# BANK34.net
KiCad netlist of a schematic drawn in Altium Designer
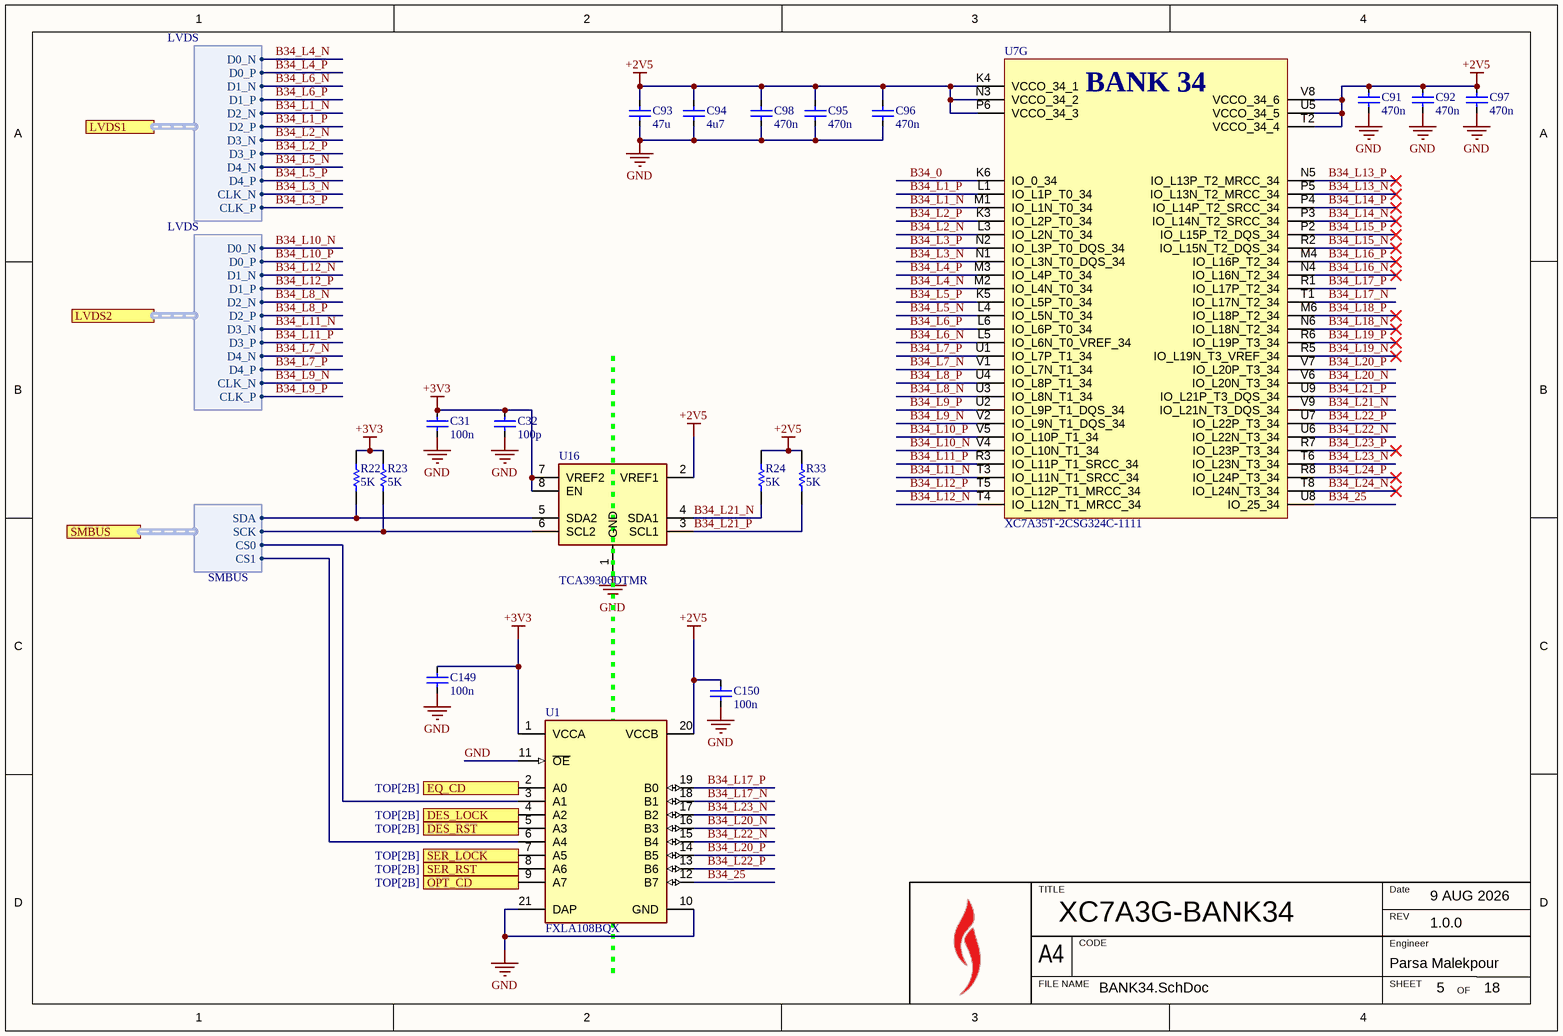
[diagram p0: BANK34.SchDoc]

(export (version "E")
  (design (tool "Eeschema 10.0.6"))
  (components
    (comp (ref "C31")
      (value "100n")
      (footprint "FP-C1005-050-0_05-IPC_C")
      (description "MLCC 100nF ±10% 50V X7R SMD 0402")
      (fields (field (name "VOLTAGE") "50V") (field (name "TOLERANCE") "10%"))
      (libsource (lib "Schlib1") (part "C1005X7R1H104K050BB"))
    )
    (comp (ref "C32")
      (value "100p")
      (footprint "FP-C1005-050-0_05-IPC_C")
      (description "MLCC 100pF ±5% 50V C0G SMD 0402")
      (fields (field (name "TOLERANCE") "5%") (field (name "VOLTAGE") "50V"))
      (libsource (lib "Schlib1") (part "C1005C0G1H101J050BA"))
    )
    (comp (ref "C91")
      (value "470n")
      (footprint "pcblib1:FP-C1005-050-0_05-IPC_C")
      (description "Multilayer Ceramic Capacitors 470nF ±10% 25V X5R SMD 0402")
      (fields (field (name "VOLTAGE") "25V") (field (name "TOLERANCE") "10%"))
      (libsource (lib "Schlib1") (part "C1005X5R1E474K050BB"))
    )
    (comp (ref "C92")
      (value "470n")
      (footprint "pcblib1:FP-C1005-050-0_05-IPC_C")
      (description "Multilayer Ceramic Capacitors 470nF ±10% 25V X5R SMD 0402")
      (fields (field (name "VOLTAGE") "25V") (field (name "TOLERANCE") "10%"))
      (libsource (lib "Schlib1") (part "C1005X5R1E474K050BB"))
    )
    (comp (ref "C93")
      (value "47u")
      (footprint "FP-C2012-125-0_2-IPC_C")
      (description "47μF ±20% 10V X5R SMD 0805 Multilayer Ceramic Capacitors")
      (fields (field (name "VOLTAGE") "10V") (field (name "TOLERANCE") "20%"))
      (libsource (lib "Schlib1") (part "C2012X5R1A476M125AC"))
    )
    (comp (ref "C94")
      (value "4u7")
      (footprint "FP-C1005-050-0_20-0_10-IPC_C")
      (description "4.7UF 10V X5R 0402")
      (fields (field (name "TOLERANCE") "10%") (field (name "PART NUMBER") "C1005X5R1A475K050BE"))
      (libsource (lib "Schlib1") (part "C1005X5R1A475K050BE"))
    )
    (comp (ref "C95")
      (value "470n")
      (footprint "pcblib1:FP-C1005-050-0_05-IPC_C")
      (description "Multilayer Ceramic Capacitors 470nF ±10% 25V X5R SMD 0402")
      (fields (field (name "VOLTAGE") "25V") (field (name "TOLERANCE") "10%"))
      (libsource (lib "Schlib1") (part "C1005X5R1E474K050BB"))
    )
    (comp (ref "C96")
      (value "470n")
      (footprint "pcblib1:FP-C1005-050-0_05-IPC_C")
      (description "Multilayer Ceramic Capacitors 470nF ±10% 25V X5R SMD 0402")
      (fields (field (name "VOLTAGE") "25V") (field (name "TOLERANCE") "10%"))
      (libsource (lib "Schlib1") (part "C1005X5R1E474K050BB"))
    )
    (comp (ref "C97")
      (value "470n")
      (footprint "pcblib1:FP-C1005-050-0_05-IPC_C")
      (description "Multilayer Ceramic Capacitors 470nF ±10% 25V X5R SMD 0402")
      (fields (field (name "VOLTAGE") "25V") (field (name "TOLERANCE") "10%"))
      (libsource (lib "Schlib1") (part "C1005X5R1E474K050BB"))
    )
    (comp (ref "C98")
      (value "470n")
      (footprint "pcblib1:FP-C1005-050-0_05-IPC_C")
      (description "Multilayer Ceramic Capacitors 470nF ±10% 25V X5R SMD 0402")
      (fields (field (name "VOLTAGE") "25V") (field (name "TOLERANCE") "10%"))
      (libsource (lib "Schlib1") (part "C1005X5R1E474K050BB"))
    )
    (comp (ref "C149")
      (value "100n")
      (footprint "FP-C1005-050-0_05-IPC_C")
      (description "MLCC 100nF ±10% 50V X7R SMD 0402")
      (fields (field (name "VOLTAGE") "50V") (field (name "TOLERANCE") "10%"))
      (libsource (lib "Schlib1") (part "C1005X7R1H104K050BB"))
    )
    (comp (ref "C150")
      (value "100n")
      (footprint "FP-C1005-050-0_05-IPC_C")
      (description "MLCC 100nF ±10% 50V X7R SMD 0402")
      (fields (field (name "VOLTAGE") "50V") (field (name "TOLERANCE") "10%"))
      (libsource (lib "Schlib1") (part "C1005X7R1H104K050BB"))
    )
    (comp (ref "R22")
      (value "5K")
      (footprint "RESC1005X40X25LL05T10")
      (description "62.5mW Thick Film Resistors 50V ±100ppm/℃ ±1% 5kΩ 0402 Chip Resistor - Surface Mount ROHS")
      (fields (field (name "MANUFACTURER") "Yageo / Phycomp") (field (name "PART NUMBER") "RC0402FR-075KL"))
      (libsource (lib "Schlib1") (part "RC0402FR-075KL"))
    )
    (comp (ref "R23")
      (value "5K")
      (footprint "RESC1005X40X25LL05T10")
      (description "62.5mW Thick Film Resistors 50V ±100ppm/℃ ±1% 5kΩ 0402 Chip Resistor - Surface Mount ROHS")
      (fields (field (name "MANUFACTURER") "Yageo / Phycomp") (field (name "PART NUMBER") "RC0402FR-075KL"))
      (libsource (lib "Schlib1") (part "RC0402FR-075KL"))
    )
    (comp (ref "R24")
      (value "5K")
      (footprint "RESC1005X40X25LL05T10")
      (description "62.5mW Thick Film Resistors 50V ±100ppm/℃ ±1% 5kΩ 0402 Chip Resistor - Surface Mount ROHS")
      (fields (field (name "MANUFACTURER") "Yageo / Phycomp") (field (name "PART NUMBER") "RC0402FR-075KL"))
      (libsource (lib "Schlib1") (part "RC0402FR-075KL"))
    )
    (comp (ref "R33")
      (value "5K")
      (footprint "RESC1005X40X25LL05T10")
      (description "62.5mW Thick Film Resistors 50V ±100ppm/℃ ±1% 5kΩ 0402 Chip Resistor - Surface Mount ROHS")
      (fields (field (name "MANUFACTURER") "Yageo / Phycomp") (field (name "PART NUMBER") "RC0402FR-075KL"))
      (libsource (lib "Schlib1") (part "RC0402FR-075KL"))
    )
    (comp (ref "U1")
      (value "FXLA108BQX")
      (footprint "FP-510CD-MFG")
      (description "IC TRNSLTR BIDIRECTIONAL 20DQFN")
      (fields
        (field (name "MANUFACTURER") "ON Semiconductor")
        (field (name "OCTOPART") "https://octopart.com/fxla108bqx-on+semiconductor-84328716")
      )
      (libsource (lib "Schlib1") (part "FXLA108BQX"))
    )
    (comp (ref "U7")
      (value "XC7A35T-2CSG324C-1111")
      (footprint "PCBLIB1:BGA324C80P18X18_1500X1500X150")
      (description "Integrated Circuit")
      (fields
        (field (name "MANUFACTURER_PART_NUMBER") "XC7A35T-2CSG324C")
        (field (name "MOUSER PART NUMBER") "217-XC7A35T-2CSG324C")
      )
      (libsource (lib "Schlib1") (part "XC7A35T-2CSG324C-1111"))
    )
    (comp (ref "U16")
      (value "TCA39306DTMR")
      (footprint "TCA39306DTMR")
      (description "Integrated Circuit")
      (fields (field (name "MOUSER PART NUMBER") "595-TCA39306DTMR"))
      (libsource (lib "Schlib1") (part "TCA39306DTMR"))
    )
  )
  (nets
    (net (code "3") (name "+2V5") (class "Default")
      (node (ref "C150") (pin "1") (pinfunction "1_1") (pintype "passive"))
      (node (ref "C91") (pin "1") (pinfunction "1_1") (pintype "passive"))
      (node (ref "C92") (pin "1") (pinfunction "1_1") (pintype "passive"))
      (node (ref "C93") (pin "1") (pinfunction "1_1") (pintype "passive"))
      (node (ref "C94") (pin "1") (pinfunction "1_1") (pintype "passive"))
      (node (ref "C95") (pin "1") (pinfunction "1_1") (pintype "passive"))
      (node (ref "C96") (pin "1") (pinfunction "1_1") (pintype "passive"))
      (node (ref "C97") (pin "1") (pinfunction "1_1") (pintype "passive"))
      (node (ref "C98") (pin "1") (pinfunction "1_1") (pintype "passive"))
      (node (ref "R24") (pin "1") (pinfunction "1_1") (pintype "passive"))
      (node (ref "R33") (pin "1") (pinfunction "1_1") (pintype "passive"))
      (node (ref "U1") (pin "20") (pinfunction "VCCB_20") (pintype "power_in"))
      (node (ref "U16") (pin "2") (pinfunction "VREF1_2") (pintype "passive"))
      (node (ref "U7") (pin "K4") (pinfunction "VCCO_34_1_K4") (pintype "passive"))
      (node (ref "U7") (pin "N3") (pinfunction "VCCO_34_2_N3") (pintype "passive"))
      (node (ref "U7") (pin "P6") (pinfunction "VCCO_34_3_P6") (pintype "passive"))
      (node (ref "U7") (pin "T2") (pinfunction "VCCO_34_4_T2") (pintype "passive"))
      (node (ref "U7") (pin "U5") (pinfunction "VCCO_34_5_U5") (pintype "passive"))
      (node (ref "U7") (pin "V8") (pinfunction "VCCO_34_6_V8") (pintype "passive"))
    )
    (net (code "4") (name "+3V3") (class "Default")
      (node (ref "C149") (pin "1") (pinfunction "1_1") (pintype "passive"))
      (node (ref "C31") (pin "1") (pinfunction "1_1") (pintype "passive"))
      (node (ref "C32") (pin "1") (pinfunction "1_1") (pintype "passive"))
      (node (ref "R22") (pin "1") (pinfunction "1_1") (pintype "passive"))
      (node (ref "R23") (pin "1") (pinfunction "1_1") (pintype "passive"))
      (node (ref "U1") (pin "1") (pinfunction "VCCA_1") (pintype "power_in"))
      (node (ref "U16") (pin "7") (pinfunction "VREF2_7") (pintype "passive"))
      (node (ref "U16") (pin "8") (pinfunction "EN_8") (pintype "passive"))
    )
    (net (code "5") (name "/B34_0") (class "Default")
      (node (ref "U7") (pin "K6") (pinfunction "IO_0_34_K6") (pintype "passive"))
    )
    (net (code "6") (name "/B34_25") (class "Default")
      (node (ref "U1") (pin "12") (pinfunction "B7_12") (pintype "bidirectional"))
      (node (ref "U7") (pin "U8") (pinfunction "IO_25_34_U8") (pintype "passive"))
    )
    (net (code "7") (name "/B34_L1_N") (class "Default")
      (node (ref "U7") (pin "M1") (pinfunction "IO_L1N_T0_34_M1") (pintype "passive"))
    )
    (net (code "8") (name "/B34_L1_P") (class "Default")
      (node (ref "U7") (pin "L1") (pinfunction "IO_L1P_T0_34_L1") (pintype "passive"))
    )
    (net (code "9") (name "/B34_L2_N") (class "Default")
      (node (ref "U7") (pin "L3") (pinfunction "IO_L2N_T0_34_L3") (pintype "passive"))
    )
    (net (code "10") (name "/B34_L2_P") (class "Default")
      (node (ref "U7") (pin "K3") (pinfunction "IO_L2P_T0_34_K3") (pintype "passive"))
    )
    (net (code "11") (name "/B34_L3_N") (class "Default")
      (node (ref "U7") (pin "N1") (pinfunction "IO_L3N_T0_DQS_34_N1") (pintype "passive"))
    )
    (net (code "12") (name "/B34_L3_P") (class "Default")
      (node (ref "U7") (pin "N2") (pinfunction "IO_L3P_T0_DQS_34_N2") (pintype "passive"))
    )
    (net (code "13") (name "/B34_L4_N") (class "Default")
      (node (ref "U7") (pin "M2") (pinfunction "IO_L4N_T0_34_M2") (pintype "passive"))
    )
    (net (code "14") (name "/B34_L4_P") (class "Default")
      (node (ref "U7") (pin "M3") (pinfunction "IO_L4P_T0_34_M3") (pintype "passive"))
    )
    (net (code "15") (name "/B34_L5_N") (class "Default")
      (node (ref "U7") (pin "L4") (pinfunction "IO_L5N_T0_34_L4") (pintype "passive"))
    )
    (net (code "16") (name "/B34_L5_P") (class "Default")
      (node (ref "U7") (pin "K5") (pinfunction "IO_L5P_T0_34_K5") (pintype "passive"))
    )
    (net (code "17") (name "/B34_L6_N") (class "Default")
      (node (ref "U7") (pin "L5") (pinfunction "IO_L6N_T0_VREF_34_L5") (pintype "passive"))
    )
    (net (code "18") (name "/B34_L6_P") (class "Default")
      (node (ref "U7") (pin "L6") (pinfunction "IO_L6P_T0_34_L6") (pintype "passive"))
    )
    (net (code "19") (name "/B34_L7_N") (class "Default")
      (node (ref "U7") (pin "V1") (pinfunction "IO_L7N_T1_34_V1") (pintype "passive"))
    )
    (net (code "20") (name "/B34_L7_P") (class "Default")
      (node (ref "U7") (pin "U1") (pinfunction "IO_L7P_T1_34_U1") (pintype "passive"))
    )
    (net (code "21") (name "/B34_L8_N") (class "Default")
      (node (ref "U7") (pin "U3") (pinfunction "IO_L8N_T1_34_U3") (pintype "passive"))
    )
    (net (code "22") (name "/B34_L8_P") (class "Default")
      (node (ref "U7") (pin "U4") (pinfunction "IO_L8P_T1_34_U4") (pintype "passive"))
    )
    (net (code "23") (name "/B34_L9_N") (class "Default")
      (node (ref "U7") (pin "V2") (pinfunction "IO_L9N_T1_DQS_34_V2") (pintype "passive"))
    )
    (net (code "24") (name "/B34_L9_P") (class "Default")
      (node (ref "U7") (pin "U2") (pinfunction "IO_L9P_T1_DQS_34_U2") (pintype "passive"))
    )
    (net (code "25") (name "/B34_L10_N") (class "Default")
      (node (ref "U7") (pin "V4") (pinfunction "IO_L10N_T1_34_V4") (pintype "passive"))
    )
    (net (code "26") (name "/B34_L10_P") (class "Default")
      (node (ref "U7") (pin "V5") (pinfunction "IO_L10P_T1_34_V5") (pintype "passive"))
    )
    (net (code "27") (name "/B34_L11_N") (class "Default")
      (node (ref "U7") (pin "T3") (pinfunction "IO_L11N_T1_SRCC_34_T3") (pintype "passive"))
    )
    (net (code "28") (name "/B34_L11_P") (class "Default")
      (node (ref "U7") (pin "R3") (pinfunction "IO_L11P_T1_SRCC_34_R3") (pintype "passive"))
    )
    (net (code "29") (name "/B34_L12_N") (class "Default")
      (node (ref "U7") (pin "T4") (pinfunction "IO_L12N_T1_MRCC_34_T4") (pintype "passive"))
    )
    (net (code "30") (name "/B34_L12_P") (class "Default")
      (node (ref "U7") (pin "T5") (pinfunction "IO_L12P_T1_MRCC_34_T5") (pintype "passive"))
    )
    (net (code "31") (name "/B34_L13_N") (class "Default")
      (node (ref "U7") (pin "P5") (pinfunction "IO_L13N_T2_MRCC_34_P5") (pintype "passive+no_connect"))
    )
    (net (code "32") (name "/B34_L13_P") (class "Default")
      (node (ref "U7") (pin "N5") (pinfunction "IO_L13P_T2_MRCC_34_N5") (pintype "passive+no_connect"))
    )
    (net (code "33") (name "/B34_L14_N") (class "Default")
      (node (ref "U7") (pin "P3") (pinfunction "IO_L14N_T2_SRCC_34_P3") (pintype "passive+no_connect"))
    )
    (net (code "34") (name "/B34_L14_P") (class "Default")
      (node (ref "U7") (pin "P4") (pinfunction "IO_L14P_T2_SRCC_34_P4") (pintype "passive+no_connect"))
    )
    (net (code "35") (name "/B34_L15_N") (class "Default")
      (node (ref "U7") (pin "R2") (pinfunction "IO_L15N_T2_DQS_34_R2") (pintype "passive+no_connect"))
    )
    (net (code "36") (name "/B34_L15_P") (class "Default")
      (node (ref "U7") (pin "P2") (pinfunction "IO_L15P_T2_DQS_34_P2") (pintype "passive+no_connect"))
    )
    (net (code "37") (name "/B34_L16_N") (class "Default")
      (node (ref "U7") (pin "N4") (pinfunction "IO_L16N_T2_34_N4") (pintype "passive+no_connect"))
    )
    (net (code "38") (name "/B34_L16_P") (class "Default")
      (node (ref "U7") (pin "M4") (pinfunction "IO_L16P_T2_34_M4") (pintype "passive+no_connect"))
    )
    (net (code "39") (name "/B34_L17_N") (class "Default")
      (node (ref "U1") (pin "18") (pinfunction "B1_18") (pintype "bidirectional"))
      (node (ref "U7") (pin "T1") (pinfunction "IO_L17N_T2_34_T1") (pintype "passive"))
    )
    (net (code "40") (name "/B34_L17_P") (class "Default")
      (node (ref "U1") (pin "19") (pinfunction "B0_19") (pintype "bidirectional"))
      (node (ref "U7") (pin "R1") (pinfunction "IO_L17P_T2_34_R1") (pintype "passive"))
    )
    (net (code "41") (name "/B34_L18_N") (class "Default")
      (node (ref "U7") (pin "N6") (pinfunction "IO_L18N_T2_34_N6") (pintype "passive+no_connect"))
    )
    (net (code "42") (name "/B34_L18_P") (class "Default")
      (node (ref "U7") (pin "M6") (pinfunction "IO_L18P_T2_34_M6") (pintype "passive+no_connect"))
    )
    (net (code "43") (name "/B34_L19_N") (class "Default")
      (node (ref "U7") (pin "R5") (pinfunction "IO_L19N_T3_VREF_34_R5") (pintype "passive+no_connect"))
    )
    (net (code "44") (name "/B34_L19_P") (class "Default")
      (node (ref "U7") (pin "R6") (pinfunction "IO_L19P_T3_34_R6") (pintype "passive+no_connect"))
    )
    (net (code "45") (name "/B34_L20_N") (class "Default")
      (node (ref "U1") (pin "16") (pinfunction "B3_16") (pintype "bidirectional"))
      (node (ref "U7") (pin "V6") (pinfunction "IO_L20N_T3_34_V6") (pintype "passive"))
    )
    (net (code "46") (name "/B34_L20_P") (class "Default")
      (node (ref "U1") (pin "14") (pinfunction "B5_14") (pintype "bidirectional"))
      (node (ref "U7") (pin "V7") (pinfunction "IO_L20P_T3_34_V7") (pintype "passive"))
    )
    (net (code "47") (name "/B34_L21_N") (class "Default")
      (node (ref "R24") (pin "2") (pinfunction "2_2") (pintype "passive"))
      (node (ref "U16") (pin "4") (pinfunction "SDA1_4") (pintype "passive"))
      (node (ref "U7") (pin "V9") (pinfunction "IO_L21N_T3_DQS_34_V9") (pintype "passive"))
    )
    (net (code "48") (name "/B34_L21_P") (class "Default")
      (node (ref "R33") (pin "2") (pinfunction "2_2") (pintype "passive"))
      (node (ref "U16") (pin "3") (pinfunction "SCL1_3") (pintype "passive"))
      (node (ref "U7") (pin "U9") (pinfunction "IO_L21P_T3_DQS_34_U9") (pintype "passive"))
    )
    (net (code "49") (name "/B34_L22_N") (class "Default")
      (node (ref "U1") (pin "15") (pinfunction "B4_15") (pintype "bidirectional"))
      (node (ref "U7") (pin "U6") (pinfunction "IO_L22N_T3_34_U6") (pintype "passive"))
    )
    (net (code "50") (name "/B34_L22_P") (class "Default")
      (node (ref "U1") (pin "13") (pinfunction "B6_13") (pintype "bidirectional"))
      (node (ref "U7") (pin "U7") (pinfunction "IO_L22P_T3_34_U7") (pintype "passive"))
    )
    (net (code "51") (name "/B34_L23_N") (class "Default")
      (node (ref "U1") (pin "17") (pinfunction "B2_17") (pintype "bidirectional"))
      (node (ref "U7") (pin "T6") (pinfunction "IO_L23N_T3_34_T6") (pintype "passive"))
    )
    (net (code "52") (name "/B34_L23_P") (class "Default")
      (node (ref "U7") (pin "R7") (pinfunction "IO_L23P_T3_34_R7") (pintype "passive+no_connect"))
    )
    (net (code "53") (name "/B34_L24_N") (class "Default")
      (node (ref "U7") (pin "T8") (pinfunction "IO_L24N_T3_34_T8") (pintype "passive+no_connect"))
    )
    (net (code "54") (name "/B34_L24_P") (class "Default")
      (node (ref "U7") (pin "R8") (pinfunction "IO_L24P_T3_34_R8") (pintype "passive+no_connect"))
    )
    (net (code "55") (name "/CS0") (class "Default")
      (node (ref "U1") (pin "3") (pinfunction "A1_3") (pintype "passive"))
    )
    (net (code "56") (name "/CS1") (class "Default")
      (node (ref "U1") (pin "6") (pinfunction "A4_6") (pintype "passive"))
    )
    (net (code "57") (name "/DES_LOCK") (class "Default")
      (node (ref "U1") (pin "4") (pinfunction "A2_4") (pintype "passive"))
    )
    (net (code "58") (name "/DES_RST") (class "Default")
      (node (ref "U1") (pin "5") (pinfunction "A3_5") (pintype "passive"))
    )
    (net (code "59") (name "/EQ_CD") (class "Default")
      (node (ref "U1") (pin "2") (pinfunction "A0_2") (pintype "passive"))
    )
    (net (code "60") (name "/OPT_CD") (class "Default")
      (node (ref "U1") (pin "9") (pinfunction "A7_9") (pintype "passive"))
    )
    (net (code "61") (name "/SCK") (class "Default")
      (node (ref "R23") (pin "2") (pinfunction "2_2") (pintype "passive"))
      (node (ref "U16") (pin "6") (pinfunction "SCL2_6") (pintype "passive"))
    )
    (net (code "62") (name "/SDA") (class "Default")
      (node (ref "R22") (pin "2") (pinfunction "2_2") (pintype "passive"))
      (node (ref "U16") (pin "5") (pinfunction "SDA2_5") (pintype "passive"))
    )
    (net (code "63") (name "/SER_LOCK") (class "Default")
      (node (ref "U1") (pin "7") (pinfunction "A5_7") (pintype "passive"))
    )
    (net (code "64") (name "/SER_RST") (class "Default")
      (node (ref "U1") (pin "8") (pinfunction "A6_8") (pintype "passive"))
    )
    (net (code "67") (name "GND") (class "Default")
      (node (ref "C149") (pin "2") (pinfunction "2_2") (pintype "passive"))
      (node (ref "C150") (pin "2") (pinfunction "2_2") (pintype "passive"))
      (node (ref "C31") (pin "2") (pinfunction "2_2") (pintype "passive"))
      (node (ref "C32") (pin "2") (pinfunction "2_2") (pintype "passive"))
      (node (ref "C91") (pin "2") (pinfunction "2_2") (pintype "passive"))
      (node (ref "C92") (pin "2") (pinfunction "2_2") (pintype "passive"))
      (node (ref "C93") (pin "2") (pinfunction "2_2") (pintype "passive"))
      (node (ref "C94") (pin "2") (pinfunction "2_2") (pintype "passive"))
      (node (ref "C95") (pin "2") (pinfunction "2_2") (pintype "passive"))
      (node (ref "C96") (pin "2") (pinfunction "2_2") (pintype "passive"))
      (node (ref "C97") (pin "2") (pinfunction "2_2") (pintype "passive"))
      (node (ref "C98") (pin "2") (pinfunction "2_2") (pintype "passive"))
      (node (ref "U1") (pin "10") (pinfunction "GND_10") (pintype "power_in"))
      (node (ref "U1") (pin "11") (pinfunction "~{OE}_11") (pintype "input"))
      (node (ref "U1") (pin "21") (pinfunction "DAP_21") (pintype "power_in"))
      (node (ref "U16") (pin "1") (pinfunction "GND_1") (pintype "passive"))
    )
  )
)
